# Power_Input.net
KiCad netlist of a schematic drawn in Altium Designer
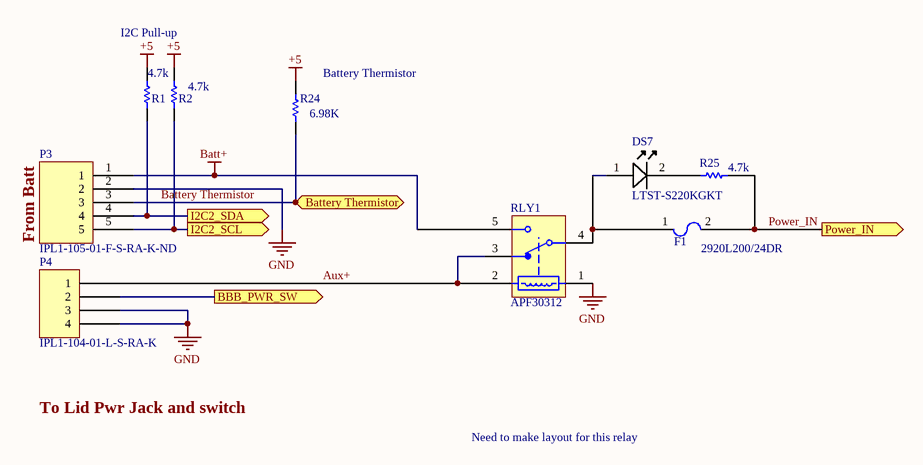
[diagram p0: Power_Input.SchDoc]

(export (version "E")
  (design (tool "Eeschema 10.0.6"))
  (components
    (comp (ref "DS7")
      (value "Lite-On LTST-S220KGKT Green LED, 571 nm 2012 (0805) Side View, Rectangle Lens SMD package")
      (footprint "0805C_L")
      (fields
        (field (name "MANUFACTURER") "Vishay / Lite-On")
        (field (name "MANUFACTURER PART NUMBER") "LTST-S220KGKT")
      )
      (libsource (lib "*") (part "LED A/K"))
    )
    (comp (ref "F1")
      (value "PCT")
      (footprint "CAPC7451X12N")
      (libsource (lib "ZLS_Schematic_lib") (part "PCT"))
    )
    (comp (ref "P3")
      (value "IPL1-105-01-F-S-RA")
      (footprint "IPL1-105-01-F-S-RA")
      (fields (field (name "SUPPLIER PART NUMBER 1") "IPL1-105-01-F-S-RA-K-ND"))
      (libsource (lib "ZLS_Schematic_lib") (part "IPL1-105-01-F-S-RA"))
    )
    (comp (ref "P4")
      (value "IPL1-104-01-L-S-RA-K")
      (footprint "IPL1-104-01-L-S-RA-K")
      (fields
        (field (name "MANUFACTURER") "Samtec Inc.")
        (field (name "MANUFACTURER PART NUMBER") "IPL1-104-01-L-S-RA-K")
      )
      (libsource (lib "ZLS_Schematic_lib") (part "IPL1-104-01-L-S-RA-K"))
    )
    (comp (ref "R1")
      (value "3K74 0.125W 1% 0805 (2012 Metric)  SMD")
      (footprint "RESC0805(2012)_N")
      (fields
        (field (name "MANUFACTURER") "Vishay Dale")
        (field (name "MANUFACTURER PART NUMBER") "CRCW08054K70FKEA")
        (field (name "RESISTANCE (OHMS)") "4.7k")
        (field (name "TOLERANCE") "±1%")
      )
      (libsource (lib "Altium Content Vault") (part "CMP-1013-00574-1"))
    )
    (comp (ref "R2")
      (value "3K74 0.125W 1% 0805 (2012 Metric)  SMD")
      (footprint "RESC0805(2012)_N")
      (fields
        (field (name "MANUFACTURER") "Vishay Dale")
        (field (name "MANUFACTURER PART NUMBER") "CRCW08054K70FKEA")
        (field (name "RESISTANCE (OHMS)") "4.7k")
        (field (name "TOLERANCE") "±1%")
      )
      (libsource (lib "Altium Content Vault") (part "CMP-1013-00574-1"))
    )
    (comp (ref "R24")
      (value "6.98K")
      (footprint "RESC0402(1005)_L")
      (description "RES SMD 6.98K OHM 1% 1/16W 0402")
      (fields
        (field (name "MANUFACTURER") "Yageo")
        (field (name "MANUFACTURER PART NUMBER") "RC0402FR-076K98L")
      )
      (libsource (lib "Altium Content Vault") (part "CMP-1011-00927-1"))
    )
    (comp (ref "R25")
      (value "RES SMD 4.7K OHM 1% 1/8W 0805")
      (footprint "RESC0805(2012)_M")
      (fields
        (field (name "MANUFACTURER") "Vishay Dale")
        (field (name "MANUFACTURER PART NUMBER") "CRCW08054K70FKEA")
        (field (name "RESISTANCE (OHMS)") "4.7k")
        (field (name "TOLERANCE") "±1%")
      )
      (libsource (lib "Altium Content Vault") (part "CMP-1013-00017-1"))
    )
    (comp (ref "RLY1")
      (value "APF30312")
      (footprint "PNSC-PF-5-2800x500x1500_V")
      (fields (field (name "MANUFACTURER") "Panasonic"))
      (libsource (lib "Altium Content Vault") (part "PNSC-APF30312-PF-5-2800x500x1500-5"))
    )
  )
  (nets
    (net (code "1") (name "+5") (class "Default")
      (node (ref "R1") (pin "2") (pinfunction "2_2") (pintype "passive"))
      (node (ref "R2") (pin "2") (pinfunction "2_2") (pintype "passive"))
      (node (ref "R24") (pin "2") (pinfunction "2_2") (pintype "passive"))
    )
    (net (code "2") (name "/Aux+") (class "Default")
      (node (ref "P4") (pin "1") (pinfunction "1_1") (pintype "passive"))
      (node (ref "RLY1") (pin "2") (pinfunction "2_2") (pintype "passive"))
      (node (ref "RLY1") (pin "3") (pinfunction "NC_3") (pintype "passive"))
    )
    (net (code "3") (name "/BBB_PWR_SW") (class "Default")
      (node (ref "P4") (pin "2") (pinfunction "2_2") (pintype "passive"))
    )
    (net (code "4") (name "/Battery Thermistor") (class "Default")
      (node (ref "P3") (pin "3") (pinfunction "3_3") (pintype "passive"))
      (node (ref "R24") (pin "1") (pinfunction "1_1") (pintype "passive"))
    )
    (net (code "5") (name "/I2C2_SCL") (class "Default")
      (node (ref "P3") (pin "5") (pinfunction "5_5") (pintype "passive"))
      (node (ref "R2") (pin "1") (pinfunction "1_1") (pintype "passive"))
    )
    (net (code "6") (name "/I2C2_SDA") (class "Default")
      (node (ref "P3") (pin "4") (pinfunction "4_4") (pintype "passive"))
      (node (ref "R1") (pin "1") (pinfunction "1_1") (pintype "passive"))
    )
    (net (code "7") (name "/Power_IN") (class "Default")
      (node (ref "F1") (pin "2") (pinfunction "2_2") (pintype "passive"))
      (node (ref "R25") (pin "1") (pinfunction "1_1") (pintype "passive"))
    )
    (net (code "8") (name "Batt+") (class "Default")
      (node (ref "P3") (pin "1") (pinfunction "1_1") (pintype "passive"))
      (node (ref "RLY1") (pin "5") (pinfunction "NO_5") (pintype "passive"))
    )
    (net (code "9") (name "GND") (class "Default")
      (node (ref "P3") (pin "2") (pinfunction "2_2") (pintype "passive"))
      (node (ref "P4") (pin "3") (pinfunction "3_3") (pintype "passive"))
      (node (ref "P4") (pin "4") (pinfunction "4_4") (pintype "passive"))
      (node (ref "RLY1") (pin "1") (pinfunction "1_1") (pintype "passive"))
    )
    (net (code "10") (name "Net-(DS7-A)") (class "Default")
      (node (ref "DS7") (pin "1") (pinfunction "A_1") (pintype "passive"))
      (node (ref "F1") (pin "1") (pinfunction "1_1") (pintype "passive"))
      (node (ref "RLY1") (pin "4") (pinfunction "COM_4") (pintype "passive"))
    )
    (net (code "11") (name "Net-(DS7-K)") (class "Default")
      (node (ref "DS7") (pin "2") (pinfunction "K_2") (pintype "passive"))
      (node (ref "R25") (pin "2") (pinfunction "2_2") (pintype "passive"))
    )
  )
)
